# 04_ESP32_UART.net
KiCad netlist of a schematic drawn in Altium Designer
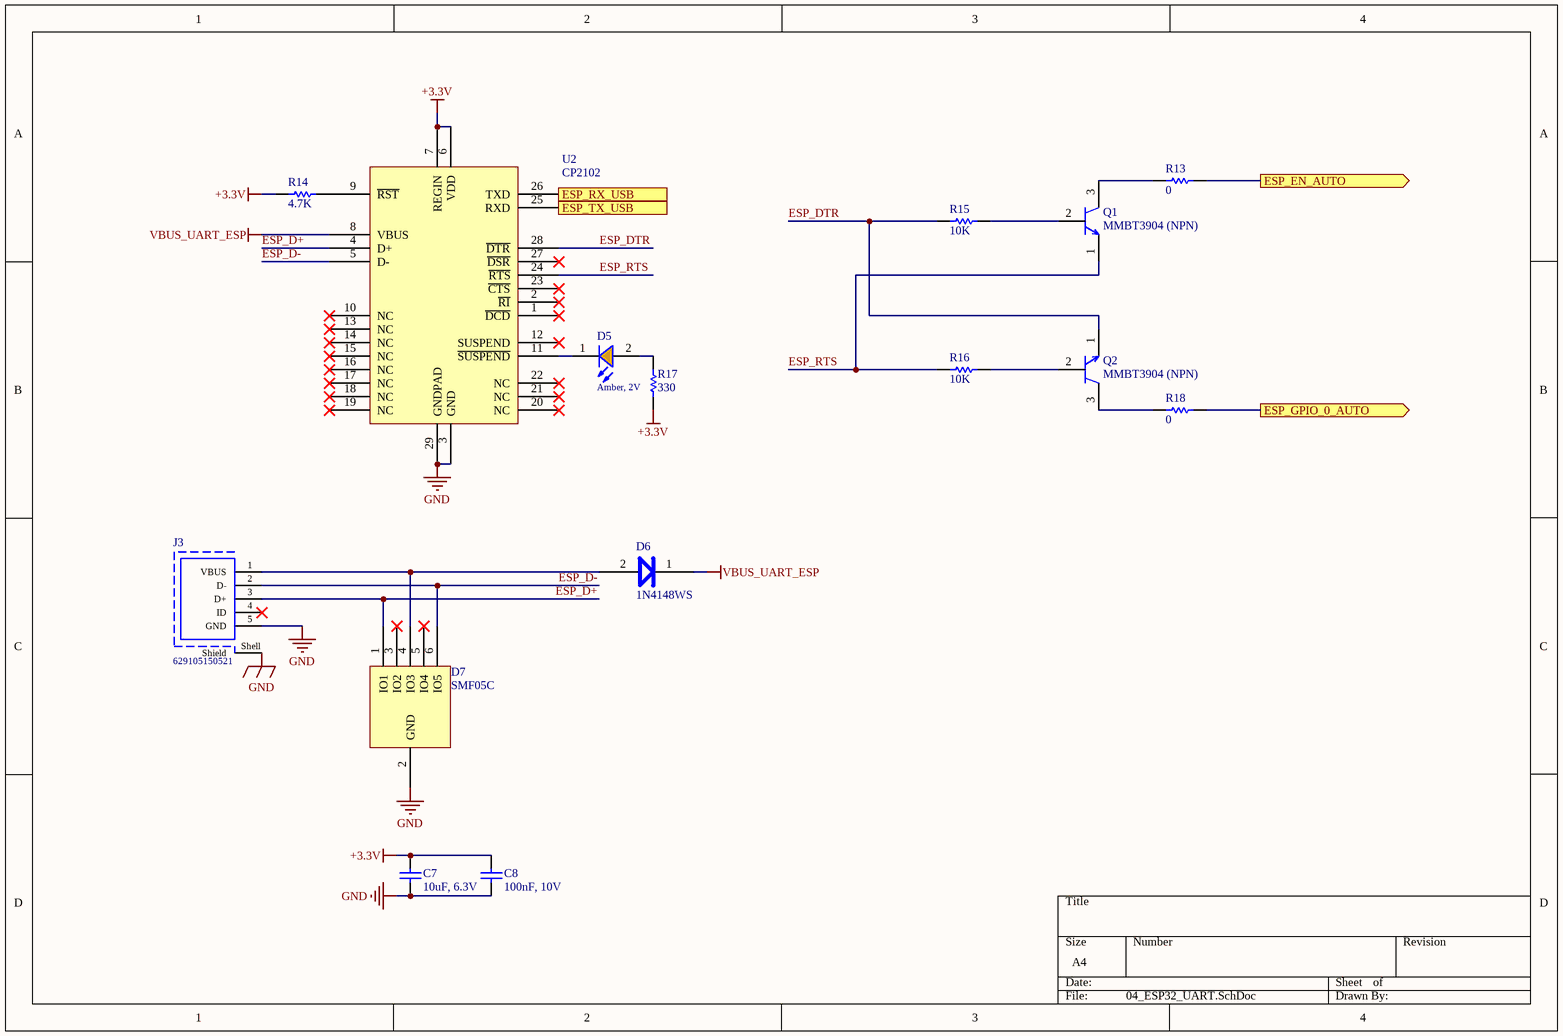
[diagram p0: 04_ESP32_UART.SchDoc]

(export (version "E")
  (design (tool "Eeschema 10.0.6"))
  (components
    (comp (ref "C7")
      (value "10uF, 6.3V")
      (footprint "WCAP-CSGP_0603_H=0.8mm_Reflow")
      (description "WCAP-CSGP Multilayer Ceramic Chip Capacitor, General Purpose, size 0603, X5R, 10uF, 6.3V")
      (fields
        (field (name "MANUFACTURER PART NUMBER") "885012106006")
        (field (name "MANUFACTURER") "Wurth Elektronik")
      )
      (libsource (lib "Altium_WCAP-CSGP (rev20a)") (part "885012106006"))
    )
    (comp (ref "C8")
      (value "100nF, 10V")
      (footprint "WCAP-CSGP_0603_H=0.8mm_Reflow")
      (description "WCAP-CSGP Multilayer Ceramic Chip Capacitor, General Purpose, size 0603, X7R, 100nF, 10V")
      (fields
        (field (name "MANUFACTURER PART NUMBER") "885012206020")
        (field (name "MANUFACTURER") "Wurth Elektronik")
      )
      (libsource (lib "Altium_WCAP-CSGP (rev20a)") (part "885012206020"))
    )
    (comp (ref "D5")
      (value "Amber, 2V")
      (footprint "WL-SMCW_0603_H=0.7mm")
      (description "WL-SMCW SMT Mono-color Chip LED Waterclear, size 0603, Amber, 2V, 140deg")
      (fields (field (name "PART NUMBER") "150060AS75000") (field (name "PUBLISHER") "Wurth Elektronik"))
      (libsource (lib "Altium_WL-SMCW (rev20a)") (part "150060AS75000"))
    )
    (comp (ref "D6")
      (value "1N4148WS")
      (footprint "SODFL250X90-2N")
      (libsource (lib "MiclsLib") (part "1N4148WS"))
    )
    (comp (ref "D7")
      (value "SMF05C")
      (footprint "SOT65P210X110-6N")
      (libsource (lib "MiclsLib") (part "SMF05C"))
    )
    (comp (ref "J3")
      (value "629105150521")
      (footprint "629105150521")
      (description "Micro USB 2.0 Type B Receptacle WR-COM, Horizontal, SMT, with Pegs, High Current at Pin 1 & Pin 5")
      (fields (field (name "PUBLISHER") "Wurth Elektronik"))
      (libsource (lib "ALTIUM-WR-COM_USB_20-rev18d") (part "629105150521"))
    )
    (comp (ref "Q1")
      (value "MMBT3904 (NPN)")
      (footprint "SOT95P245X110-3N")
      (fields (field (name "MANUFACTURER") "On Semiconductor"))
      (libsource (lib "MiclsLib") (part "MMBT3904 (NPN)"))
    )
    (comp (ref "Q2")
      (value "MMBT3904 (NPN)")
      (footprint "SOT95P245X110-3N")
      (fields (field (name "MANUFACTURER") "On Semiconductor"))
      (libsource (lib "MiclsLib") (part "MMBT3904 (NPN)"))
    )
    (comp (ref "R13")
      (value "0")
      (footprint "RES-SM-0603")
      (description "Resistor")
      (fields (field (name "Comment") "RESISTOR SMD"))
      (libsource (lib "PIF_Library") (part "RESISTOR SMD"))
    )
    (comp (ref "R14")
      (value "4.7K")
      (footprint "RES-SM-0603")
      (description "Resistor")
      (fields (field (name "Comment") "RESISTOR SMD"))
      (libsource (lib "PIF_Library") (part "RESISTOR SMD"))
    )
    (comp (ref "R15")
      (value "10K")
      (footprint "RES-SM-0603")
      (description "Resistor")
      (fields (field (name "Comment") "RESISTOR SMD"))
      (libsource (lib "PIF_Library") (part "RESISTOR SMD"))
    )
    (comp (ref "R16")
      (value "10K")
      (footprint "RES-SM-0603")
      (description "Resistor")
      (fields (field (name "Comment") "RESISTOR SMD"))
      (libsource (lib "PIF_Library") (part "RESISTOR SMD"))
    )
    (comp (ref "R17")
      (value "330")
      (footprint "RES-SM-0603")
      (description "Resistor")
      (fields (field (name "Comment") "RESISTOR SMD"))
      (libsource (lib "PIF_Library") (part "RESISTOR SMD"))
    )
    (comp (ref "R18")
      (value "0")
      (footprint "RES-SM-0603")
      (description "Resistor")
      (fields (field (name "Comment") "RESISTOR SMD"))
      (libsource (lib "PIF_Library") (part "RESISTOR SMD"))
    )
    (comp (ref "U2")
      (value "CP2102")
      (footprint "QFN50P500X500X90_HS-29N")
      (libsource (lib "MiclsLib") (part "CP2102"))
    )
  )
  (nets
    (net (code "1") (name "+3.3V") (class "Default")
      (node (ref "C7") (pin "2") (pinfunction "2_2") (pintype "passive"))
      (node (ref "C8") (pin "2") (pinfunction "2_2") (pintype "passive"))
      (node (ref "R14") (pin "2") (pinfunction "2_2") (pintype "passive"))
      (node (ref "R17") (pin "2") (pinfunction "2_2") (pintype "passive"))
      (node (ref "U2") (pin "6") (pinfunction "VDD_6") (pintype "passive"))
      (node (ref "U2") (pin "7") (pinfunction "REGIN_7") (pintype "passive"))
    )
    (net (code "2") (name "/ESP_D+") (class "Default")
      (node (ref "D7") (pin "1") (pinfunction "IO1_1") (pintype "passive"))
      (node (ref "J3") (pin "3") (pinfunction "D+_3") (pintype "passive"))
      (node (ref "U2") (pin "4") (pinfunction "D+_4") (pintype "passive"))
    )
    (net (code "3") (name "/ESP_D-") (class "Default")
      (node (ref "D7") (pin "6") (pinfunction "IO5_6") (pintype "passive"))
      (node (ref "J3") (pin "2") (pinfunction "D-_2") (pintype "passive"))
      (node (ref "U2") (pin "5") (pinfunction "D-_5") (pintype "passive"))
    )
    (net (code "4") (name "/ESP_DTR") (class "Default")
      (node (ref "Q2") (pin "1") (pinfunction "1_1") (pintype "passive"))
      (node (ref "R15") (pin "1") (pinfunction "1_1") (pintype "passive"))
      (node (ref "U2") (pin "28") (pinfunction "~{DTR}_28") (pintype "passive"))
    )
    (net (code "5") (name "/ESP_EN_AUTO") (class "Default")
      (node (ref "R13") (pin "2") (pinfunction "2_2") (pintype "passive"))
    )
    (net (code "6") (name "/ESP_GPIO_0_AUTO") (class "Default")
      (node (ref "R18") (pin "2") (pinfunction "2_2") (pintype "passive"))
    )
    (net (code "7") (name "/ESP_RTS") (class "Default")
      (node (ref "Q1") (pin "1") (pinfunction "1_1") (pintype "passive"))
      (node (ref "R16") (pin "1") (pinfunction "1_1") (pintype "passive"))
      (node (ref "U2") (pin "24") (pinfunction "~{RTS}_24") (pintype "passive"))
    )
    (net (code "8") (name "/ESP_RX_USB") (class "Default")
      (node (ref "U2") (pin "26") (pinfunction "TXD_26") (pintype "passive"))
    )
    (net (code "9") (name "/ESP_TX_USB") (class "Default")
      (node (ref "U2") (pin "25") (pinfunction "RXD_25") (pintype "passive"))
    )
    (net (code "10") (name "GND") (class "Default")
      (node (ref "C7") (pin "1") (pinfunction "1_1") (pintype "passive"))
      (node (ref "C8") (pin "1") (pinfunction "1_1") (pintype "passive"))
      (node (ref "D7") (pin "2") (pinfunction "GND_2") (pintype "passive"))
      (node (ref "J3") (pin "5") (pinfunction "GND_5") (pintype "passive"))
      (node (ref "J3") (pin "Shell") (pinfunction "Shield_Shell") (pintype "passive"))
      (node (ref "U2") (pin "29") (pinfunction "GNDPAD_29") (pintype "passive"))
      (node (ref "U2") (pin "3") (pinfunction "GND_3") (pintype "passive"))
    )
    (net (code "11") (name "Net-(D5-A)") (class "Default")
      (node (ref "D5") (pin "2") (pinfunction "A_2") (pintype "passive"))
      (node (ref "R17") (pin "1") (pinfunction "1_1") (pintype "passive"))
    )
    (net (code "12") (name "Net-(D5-K)") (class "Default")
      (node (ref "D5") (pin "1") (pinfunction "K_1") (pintype "passive"))
      (node (ref "U2") (pin "11") (pinfunction "~{SUSPEND}_11") (pintype "passive"))
    )
    (net (code "13") (name "Net-(D7-IO3)") (class "Default")
      (node (ref "D6") (pin "2") (pinfunction "2_2") (pintype "passive"))
      (node (ref "D7") (pin "4") (pinfunction "IO3_4") (pintype "passive"))
      (node (ref "J3") (pin "1") (pinfunction "VBUS_1") (pintype "passive"))
    )
    (net (code "14") (name "Net-(Q1-Pad2)") (class "Default")
      (node (ref "Q1") (pin "2") (pinfunction "2_2") (pintype "passive"))
      (node (ref "R15") (pin "2") (pinfunction "2_2") (pintype "passive"))
    )
    (net (code "15") (name "Net-(Q1-Pad3)") (class "Default")
      (node (ref "Q1") (pin "3") (pinfunction "3_3") (pintype "passive"))
      (node (ref "R13") (pin "1") (pinfunction "1_1") (pintype "passive"))
    )
    (net (code "16") (name "Net-(Q2-Pad2)") (class "Default")
      (node (ref "Q2") (pin "2") (pinfunction "2_2") (pintype "passive"))
      (node (ref "R16") (pin "2") (pinfunction "2_2") (pintype "passive"))
    )
    (net (code "17") (name "Net-(Q2-Pad3)") (class "Default")
      (node (ref "Q2") (pin "3") (pinfunction "3_3") (pintype "passive"))
      (node (ref "R18") (pin "1") (pinfunction "1_1") (pintype "passive"))
    )
    (net (code "18") (name "Net-(U2-~{RST})") (class "Default")
      (node (ref "R14") (pin "1") (pinfunction "1_1") (pintype "passive"))
      (node (ref "U2") (pin "9") (pinfunction "~{RST}_9") (pintype "passive"))
    )
    (net (code "19") (name "VBUS_UART_ESP") (class "Default")
      (node (ref "D6") (pin "1") (pinfunction "1_1") (pintype "passive"))
      (node (ref "U2") (pin "8") (pinfunction "VBUS_8") (pintype "passive"))
    )
    (net (code "20") (name "unconnected-(D7-IO2-Pad3)") (class "Default")
      (node (ref "D7") (pin "3") (pinfunction "IO2_3") (pintype "passive+no_connect"))
    )
    (net (code "21") (name "unconnected-(D7-IO4-Pad5)") (class "Default")
      (node (ref "D7") (pin "5") (pinfunction "IO4_5") (pintype "passive+no_connect"))
    )
    (net (code "22") (name "unconnected-(J3-ID-Pad4)") (class "Default")
      (node (ref "J3") (pin "4") (pinfunction "ID_4") (pintype "passive+no_connect"))
    )
    (net (code "23") (name "unconnected-(U2-NC-Pad10)") (class "Default")
      (node (ref "U2") (pin "10") (pinfunction "NC_10") (pintype "passive+no_connect"))
    )
    (net (code "24") (name "unconnected-(U2-NC-Pad13)") (class "Default")
      (node (ref "U2") (pin "13") (pinfunction "NC_13") (pintype "passive+no_connect"))
    )
    (net (code "25") (name "unconnected-(U2-NC-Pad14)") (class "Default")
      (node (ref "U2") (pin "14") (pinfunction "NC_14") (pintype "passive+no_connect"))
    )
    (net (code "26") (name "unconnected-(U2-NC-Pad15)") (class "Default")
      (node (ref "U2") (pin "15") (pinfunction "NC_15") (pintype "passive+no_connect"))
    )
    (net (code "27") (name "unconnected-(U2-NC-Pad16)") (class "Default")
      (node (ref "U2") (pin "16") (pinfunction "NC_16") (pintype "passive+no_connect"))
    )
    (net (code "28") (name "unconnected-(U2-NC-Pad17)") (class "Default")
      (node (ref "U2") (pin "17") (pinfunction "NC_17") (pintype "passive+no_connect"))
    )
    (net (code "29") (name "unconnected-(U2-NC-Pad18)") (class "Default")
      (node (ref "U2") (pin "18") (pinfunction "NC_18") (pintype "passive+no_connect"))
    )
    (net (code "30") (name "unconnected-(U2-NC-Pad19)") (class "Default")
      (node (ref "U2") (pin "19") (pinfunction "NC_19") (pintype "passive+no_connect"))
    )
    (net (code "31") (name "unconnected-(U2-NC-Pad20)") (class "Default")
      (node (ref "U2") (pin "20") (pinfunction "NC_20") (pintype "passive+no_connect"))
    )
    (net (code "32") (name "unconnected-(U2-NC-Pad21)") (class "Default")
      (node (ref "U2") (pin "21") (pinfunction "NC_21") (pintype "passive+no_connect"))
    )
    (net (code "33") (name "unconnected-(U2-NC-Pad22)") (class "Default")
      (node (ref "U2") (pin "22") (pinfunction "NC_22") (pintype "passive+no_connect"))
    )
    (net (code "34") (name "unconnected-(U2-SUSPEND-Pad12)") (class "Default")
      (node (ref "U2") (pin "12") (pinfunction "SUSPEND_12") (pintype "passive+no_connect"))
    )
    (net (code "35") (name "unconnected-(U2-~{CTS}-Pad23)") (class "Default")
      (node (ref "U2") (pin "23") (pinfunction "~{CTS}_23") (pintype "passive+no_connect"))
    )
    (net (code "36") (name "unconnected-(U2-~{DCD}-Pad1)") (class "Default")
      (node (ref "U2") (pin "1") (pinfunction "~{DCD}_1") (pintype "passive+no_connect"))
    )
    (net (code "37") (name "unconnected-(U2-~{DSR}-Pad27)") (class "Default")
      (node (ref "U2") (pin "27") (pinfunction "~{DSR}_27") (pintype "passive+no_connect"))
    )
    (net (code "38") (name "unconnected-(U2-~{RI}-Pad2)") (class "Default")
      (node (ref "U2") (pin "2") (pinfunction "~{RI}_2") (pintype "passive+no_connect"))
    )
  )
)
